# Schematic.net
KiCad netlist of a schematic drawn in EAGLE
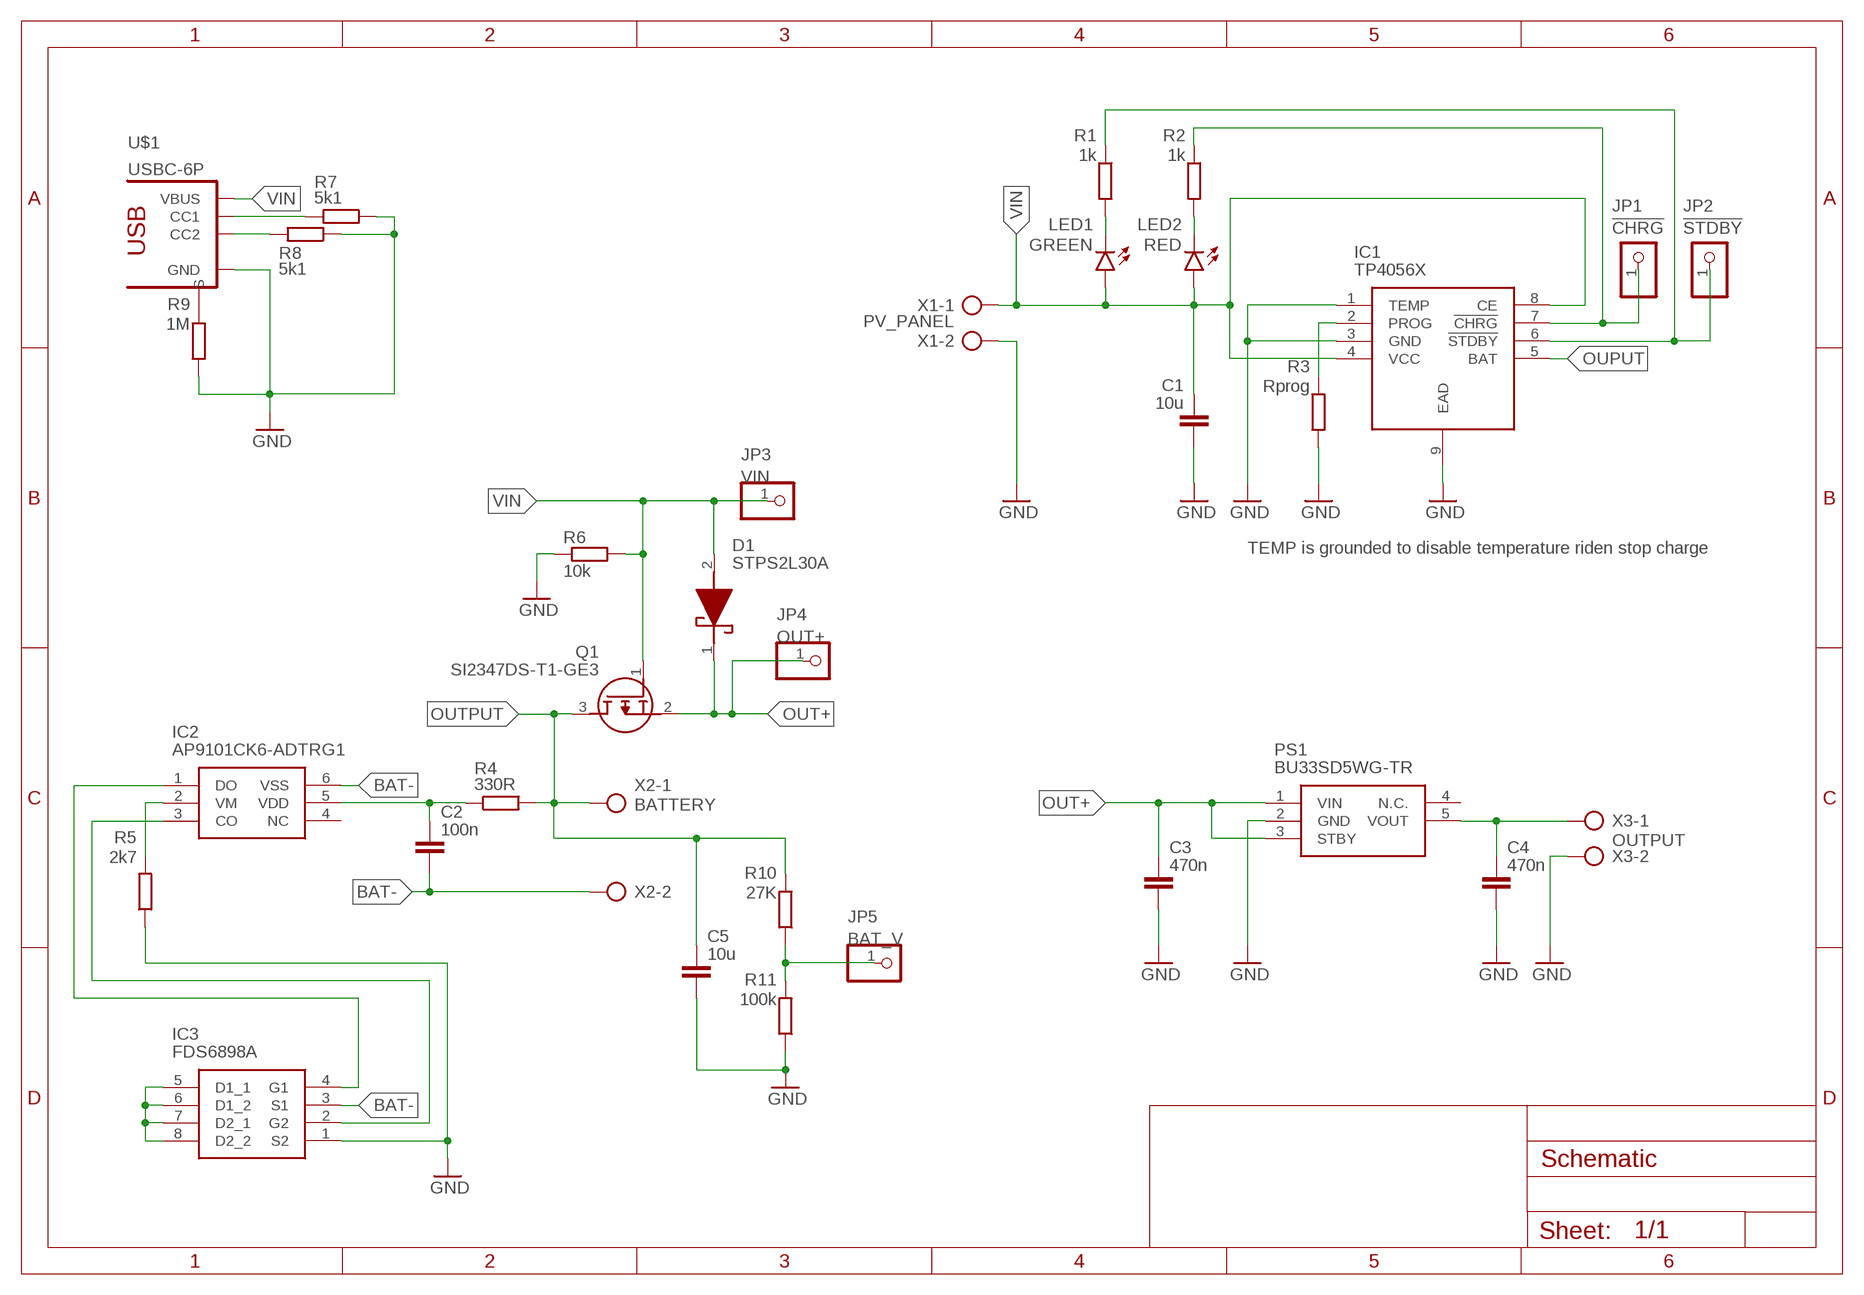
[diagram p0: schematic, sheet 1]

(export (version "E")
  (design (tool "Eeschema 10.0.6"))
  (components
    (comp (ref "C1")
      (value "10u")
      (footprint "eagle-import:C0805")
      (libsource (lib "eagle-import") (part "C-EUC0805"))
    )
    (comp (ref "C2")
      (value "100n")
      (footprint "eagle-import:C0805")
      (libsource (lib "eagle-import") (part "C-EUC0805"))
    )
    (comp (ref "C3")
      (value "470n")
      (footprint "eagle-import:C0805")
      (libsource (lib "eagle-import") (part "C-EUC0805"))
    )
    (comp (ref "C4")
      (value "470n")
      (footprint "eagle-import:C0805")
      (libsource (lib "eagle-import") (part "C-EUC0805"))
    )
    (comp (ref "C5")
      (value "10u")
      (footprint "eagle-import:C0805")
      (libsource (lib "eagle-import") (part "C-EUC0805"))
    )
    (comp (ref "D1")
      (value "STPS2L30A")
      (footprint "eagle-import:DIOM5126X265N")
      (fields (field (name "MOUSER_PART_NUMBER") "511-STPS2L30A"))
      (libsource (lib "eagle-import") (part "STPS2L30A"))
    )
    (comp (ref "IC1")
      (value "TP4056X")
      (footprint "eagle-import:SOIC127P600X175-9N")
      (libsource (lib "eagle-import") (part "TP4056X"))
    )
    (comp (ref "IC2")
      (value "AP9101CK6-ADTRG1")
      (footprint "eagle-import:SOT95P285X140-6N")
      (fields (field (name "MOUSER_PART_NUMBER") "621-AP9101CK6-ADTRG1"))
      (libsource (lib "eagle-import") (part "AP9101CK6-ADTRG1"))
    )
    (comp (ref "IC3")
      (value "FDS6898A")
      (footprint "eagle-import:SOIC127P600X175-8N")
      (fields (field (name "MOUSER_PART_NUMBER") "512-FDS6898A"))
      (libsource (lib "eagle-import") (part "FDS6898A"))
    )
    (comp (ref "JP1")
      (value "!CHRG")
      (footprint "eagle-import:1X01")
      (libsource (lib "eagle-import") (part "PINHD-1X1"))
    )
    (comp (ref "JP2")
      (value "!STDBY")
      (footprint "eagle-import:1X01")
      (libsource (lib "eagle-import") (part "PINHD-1X1"))
    )
    (comp (ref "JP3")
      (value "VIN")
      (footprint "eagle-import:1X01")
      (fields (field (name "SPICEPREFIX") "X"))
      (libsource (lib "eagle-import") (part "PINHD-1X1"))
    )
    (comp (ref "JP4")
      (value "OUT+")
      (footprint "eagle-import:1X01")
      (libsource (lib "eagle-import") (part "PINHD-1X1"))
    )
    (comp (ref "JP5")
      (value "BAT_V")
      (footprint "eagle-import:1X01")
      (libsource (lib "eagle-import") (part "PINHD-1X1"))
    )
    (comp (ref "LED1")
      (value "GREEN")
      (footprint "eagle-import:CHIPLED_0805")
      (libsource (lib "eagle-import") (part "LEDCHIPLED_0805"))
    )
    (comp (ref "LED2")
      (value "RED")
      (footprint "eagle-import:CHIPLED_0805")
      (libsource (lib "eagle-import") (part "LEDCHIPLED_0805"))
    )
    (comp (ref "PS1")
      (value "BU33SD5WG-TR")
      (footprint "eagle-import:SOT95P280X125-5N")
      (fields (field (name "MOUSER_PART_NUMBER") "755-BU33SD5WG-TR"))
      (libsource (lib "eagle-import") (part "BU33SD5WG-TR"))
    )
    (comp (ref "Q1")
      (value "SI2347DS-T1-GE3")
      (footprint "eagle-import:SOT95P237X112-3N")
      (fields
        (field (name "MANUFACTURER_PART_NUMBER") "Si2347DS-T1-GE3")
        (field (name "MOUSER_PART_NUMBER") "78-SI2347DS-T1-GE3")
      )
      (libsource (lib "eagle-import") (part "SI2347DS-T1-GE3"))
    )
    (comp (ref "R1")
      (value "1k")
      (footprint "eagle-import:R0805")
      (libsource (lib "eagle-import") (part "R-EU_R0805"))
    )
    (comp (ref "R2")
      (value "1k")
      (footprint "eagle-import:R0805")
      (libsource (lib "eagle-import") (part "R-EU_R0805"))
    )
    (comp (ref "R3")
      (value "Rprog")
      (footprint "eagle-import:R0805")
      (libsource (lib "eagle-import") (part "R-EU_R0805"))
    )
    (comp (ref "R4")
      (value "330R")
      (footprint "eagle-import:R0805")
      (libsource (lib "eagle-import") (part "R-EU_R0805"))
    )
    (comp (ref "R5")
      (value "2k7")
      (footprint "eagle-import:R0805")
      (libsource (lib "eagle-import") (part "R-EU_R0805"))
    )
    (comp (ref "R6")
      (value "10k")
      (footprint "eagle-import:R0805")
      (libsource (lib "eagle-import") (part "R-EU_R0805"))
    )
    (comp (ref "R7")
      (value "5k1")
      (footprint "eagle-import:R0805")
      (libsource (lib "eagle-import") (part "R-EU_R0805"))
    )
    (comp (ref "R8")
      (value "5k1")
      (footprint "eagle-import:R0805")
      (libsource (lib "eagle-import") (part "R-EU_R0805"))
    )
    (comp (ref "R9")
      (value "1M")
      (footprint "eagle-import:R0805")
      (libsource (lib "eagle-import") (part "R-EU_R0805"))
    )
    (comp (ref "R10")
      (value "27K")
      (footprint "eagle-import:R0805")
      (libsource (lib "eagle-import") (part "R-EU_R0805"))
    )
    (comp (ref "R11")
      (value "100k")
      (footprint "eagle-import:R0805")
      (libsource (lib "eagle-import") (part "R-EU_R0805"))
    )
    (comp (ref "U$1")
      (value "USBC-6P")
      (footprint "eagle-import:USCX-06FX-XXMX-01")
      (libsource (lib "eagle-import") (part "USBC-6P"))
    )
    (comp (ref "X1")
      (value "PV_PANEL")
      (footprint "eagle-import:AK300_2")
      (libsource (lib "eagle-import") (part "AK300/2"))
    )
    (comp (ref "X2")
      (value "BATTERY")
      (footprint "eagle-import:AK300_2")
      (libsource (lib "eagle-import") (part "AK300/2"))
    )
    (comp (ref "X3")
      (value "OUTPUT")
      (footprint "eagle-import:AK300_2")
      (libsource (lib "eagle-import") (part "AK300/2"))
    )
  )
  (nets
    (net (code "1") (name "BAT-") (class "Default")
      (node (ref "C2") (pin "2") (pinfunction "2_2") (pintype "passive"))
      (node (ref "IC2") (pin "6") (pinfunction "VSS_6") (pintype "bidirectional"))
      (node (ref "IC3") (pin "3") (pinfunction "S1_3") (pintype "bidirectional"))
      (node (ref "X2") (pin "2") (pinfunction "KL_2") (pintype "passive"))
    )
    (net (code "2") (name "GND") (class "Default")
      (node (ref "C1") (pin "2") (pinfunction "2_2") (pintype "passive"))
      (node (ref "C3") (pin "2") (pinfunction "2_2") (pintype "passive"))
      (node (ref "C4") (pin "2") (pinfunction "2_2") (pintype "passive"))
      (node (ref "C5") (pin "2") (pinfunction "2_2") (pintype "passive"))
      (node (ref "IC1") (pin "1") (pinfunction "TEMP_1") (pintype "bidirectional"))
      (node (ref "IC1") (pin "3") (pinfunction "GND_3") (pintype "bidirectional"))
      (node (ref "IC1") (pin "9") (pinfunction "EAD_9") (pintype "bidirectional"))
      (node (ref "IC3") (pin "1") (pinfunction "S2_1") (pintype "bidirectional"))
      (node (ref "PS1") (pin "2") (pinfunction "GND_2") (pintype "bidirectional"))
      (node (ref "R11") (pin "1") (pinfunction "1_1") (pintype "passive"))
      (node (ref "R3") (pin "2") (pinfunction "2_2") (pintype "passive"))
      (node (ref "R5") (pin "1") (pinfunction "1_1") (pintype "passive"))
      (node (ref "R6") (pin "1") (pinfunction "1_1") (pintype "passive"))
      (node (ref "R7") (pin "1") (pinfunction "1_1") (pintype "passive"))
      (node (ref "R8") (pin "1") (pinfunction "1_1") (pintype "passive"))
      (node (ref "R9") (pin "2") (pinfunction "2_2") (pintype "passive"))
      (node (ref "U$1") (pin "GND1") (pinfunction "GND_GND1") (pintype "power_in"))
      (node (ref "U$1") (pin "GND2") (pinfunction "GND_GND2") (pintype "power_in"))
      (node (ref "X1") (pin "2") (pinfunction "KL_2") (pintype "passive"))
      (node (ref "X3") (pin "2") (pinfunction "KL_2") (pintype "passive"))
    )
    (net (code "3") (name "Net-(IC1-PROG)") (class "Default")
      (node (ref "IC1") (pin "2") (pinfunction "PROG_2") (pintype "bidirectional"))
      (node (ref "R3") (pin "1") (pinfunction "1_1") (pintype "passive"))
    )
    (net (code "4") (name "Net-(IC1-~{CHRG})") (class "Default")
      (node (ref "IC1") (pin "7") (pinfunction "~{CHRG}_7") (pintype "bidirectional"))
      (node (ref "JP1") (pin "1") (pinfunction "1_1") (pintype "passive"))
      (node (ref "R2") (pin "1") (pinfunction "1_1") (pintype "passive"))
    )
    (net (code "5") (name "Net-(IC1-~{STDBY})") (class "Default")
      (node (ref "IC1") (pin "6") (pinfunction "~{STDBY}_6") (pintype "bidirectional"))
      (node (ref "JP2") (pin "1") (pinfunction "1_1") (pintype "passive"))
      (node (ref "R1") (pin "1") (pinfunction "1_1") (pintype "passive"))
    )
    (net (code "6") (name "Net-(IC2-CO)") (class "Default")
      (node (ref "IC2") (pin "3") (pinfunction "CO_3") (pintype "bidirectional"))
      (node (ref "IC3") (pin "2") (pinfunction "G2_2") (pintype "bidirectional"))
    )
    (net (code "7") (name "Net-(IC2-DO)") (class "Default")
      (node (ref "IC2") (pin "1") (pinfunction "DO_1") (pintype "bidirectional"))
      (node (ref "IC3") (pin "4") (pinfunction "G1_4") (pintype "bidirectional"))
    )
    (net (code "8") (name "Net-(IC2-VDD)") (class "Default")
      (node (ref "C2") (pin "1") (pinfunction "1_1") (pintype "passive"))
      (node (ref "IC2") (pin "5") (pinfunction "VDD_5") (pintype "bidirectional"))
      (node (ref "R4") (pin "1") (pinfunction "1_1") (pintype "passive"))
    )
    (net (code "9") (name "Net-(IC2-VM)") (class "Default")
      (node (ref "IC2") (pin "2") (pinfunction "VM_2") (pintype "bidirectional"))
      (node (ref "R5") (pin "2") (pinfunction "2_2") (pintype "passive"))
    )
    (net (code "10") (name "Net-(IC3-D1_1)") (class "Default")
      (node (ref "IC3") (pin "5") (pinfunction "D1_1_5") (pintype "bidirectional"))
      (node (ref "IC3") (pin "6") (pinfunction "D1_2_6") (pintype "bidirectional"))
      (node (ref "IC3") (pin "7") (pinfunction "D2_1_7") (pintype "bidirectional"))
      (node (ref "IC3") (pin "8") (pinfunction "D2_2_8") (pintype "bidirectional"))
    )
    (net (code "11") (name "Net-(JP5-Pad1)") (class "Default")
      (node (ref "JP5") (pin "1") (pinfunction "1_1") (pintype "passive"))
      (node (ref "R10") (pin "1") (pinfunction "1_1") (pintype "passive"))
      (node (ref "R11") (pin "2") (pinfunction "2_2") (pintype "passive"))
    )
    (net (code "12") (name "Net-(LED1-PadC)") (class "Default")
      (node (ref "LED1") (pin "C") (pinfunction "C_C") (pintype "passive"))
      (node (ref "R1") (pin "2") (pinfunction "2_2") (pintype "passive"))
    )
    (net (code "13") (name "Net-(LED2-PadC)") (class "Default")
      (node (ref "LED2") (pin "C") (pinfunction "C_C") (pintype "passive"))
      (node (ref "R2") (pin "2") (pinfunction "2_2") (pintype "passive"))
    )
    (net (code "14") (name "Net-(PS1-VOUT)") (class "Default")
      (node (ref "C4") (pin "1") (pinfunction "1_1") (pintype "passive"))
      (node (ref "PS1") (pin "5") (pinfunction "VOUT_5") (pintype "bidirectional"))
      (node (ref "X3") (pin "1") (pinfunction "KL_1") (pintype "passive"))
    )
    (net (code "15") (name "Net-(R7-Pad2)") (class "Default")
      (node (ref "R7") (pin "2") (pinfunction "2_2") (pintype "passive"))
      (node (ref "U$1") (pin "CC1") (pinfunction "CC1_CC1") (pintype "bidirectional"))
    )
    (net (code "16") (name "Net-(R8-Pad2)") (class "Default")
      (node (ref "R8") (pin "2") (pinfunction "2_2") (pintype "passive"))
      (node (ref "U$1") (pin "CC2") (pinfunction "CC2_CC2") (pintype "bidirectional"))
    )
    (net (code "17") (name "Net-(R9-Pad1)") (class "Default")
      (node (ref "R9") (pin "1") (pinfunction "1_1") (pintype "passive"))
      (node (ref "U$1") (pin "SHIELD1") (pinfunction "S_SHIELD1") (pintype "passive"))
      (node (ref "U$1") (pin "SHIELD2") (pinfunction "S_SHIELD2") (pintype "passive"))
      (node (ref "U$1") (pin "SHIELD3") (pinfunction "S_SHIELD3") (pintype "passive"))
      (node (ref "U$1") (pin "SHIELD4") (pinfunction "S_SHIELD4") (pintype "passive"))
    )
    (net (code "18") (name "OUPUT") (class "Default")
      (node (ref "IC1") (pin "5") (pinfunction "BAT_5") (pintype "bidirectional"))
    )
    (net (code "19") (name "OUT+") (class "Default")
      (node (ref "C3") (pin "1") (pinfunction "1_1") (pintype "passive"))
      (node (ref "D1") (pin "1") (pinfunction "K_1") (pintype "bidirectional"))
      (node (ref "JP4") (pin "1") (pinfunction "1_1") (pintype "passive"))
      (node (ref "PS1") (pin "1") (pinfunction "VIN_1") (pintype "bidirectional"))
      (node (ref "PS1") (pin "3") (pinfunction "STBY_3") (pintype "bidirectional"))
      (node (ref "Q1") (pin "2") (pinfunction "S_2") (pintype "bidirectional"))
    )
    (net (code "20") (name "OUTPUT") (class "Default")
      (node (ref "C5") (pin "1") (pinfunction "1_1") (pintype "passive"))
      (node (ref "Q1") (pin "3") (pinfunction "D_3") (pintype "bidirectional"))
      (node (ref "R10") (pin "2") (pinfunction "2_2") (pintype "passive"))
      (node (ref "R4") (pin "2") (pinfunction "2_2") (pintype "passive"))
      (node (ref "X2") (pin "1") (pinfunction "KL_1") (pintype "passive"))
    )
    (net (code "21") (name "VIN") (class "Default")
      (node (ref "C1") (pin "1") (pinfunction "1_1") (pintype "passive"))
      (node (ref "D1") (pin "2") (pinfunction "A_2") (pintype "bidirectional"))
      (node (ref "IC1") (pin "4") (pinfunction "VCC_4") (pintype "bidirectional"))
      (node (ref "IC1") (pin "8") (pinfunction "CE_8") (pintype "bidirectional"))
      (node (ref "JP3") (pin "1") (pinfunction "1_1") (pintype "passive"))
      (node (ref "LED1") (pin "A") (pinfunction "A_A") (pintype "passive"))
      (node (ref "LED2") (pin "A") (pinfunction "A_A") (pintype "passive"))
      (node (ref "Q1") (pin "1") (pinfunction "G_1") (pintype "bidirectional"))
      (node (ref "R6") (pin "2") (pinfunction "2_2") (pintype "passive"))
      (node (ref "U$1") (pin "VBUS1") (pinfunction "VBUS_VBUS1") (pintype "power_in"))
      (node (ref "U$1") (pin "VBUS2") (pinfunction "VBUS_VBUS2") (pintype "power_in"))
      (node (ref "X1") (pin "1") (pinfunction "KL_1") (pintype "passive"))
    )
    (net (code "22") (name "unconnected-(IC2-NC-Pad4)") (class "Default")
      (node (ref "IC2") (pin "4") (pinfunction "NC_4") (pintype "no_connect"))
    )
    (net (code "23") (name "unconnected-(PS1-N.C.-Pad4)") (class "Default")
      (node (ref "PS1") (pin "4") (pinfunction "N.C._4") (pintype "no_connect"))
    )
  )
)
